# MAIN_CONN.net
KiCad netlist of a schematic drawn in Altium Designer
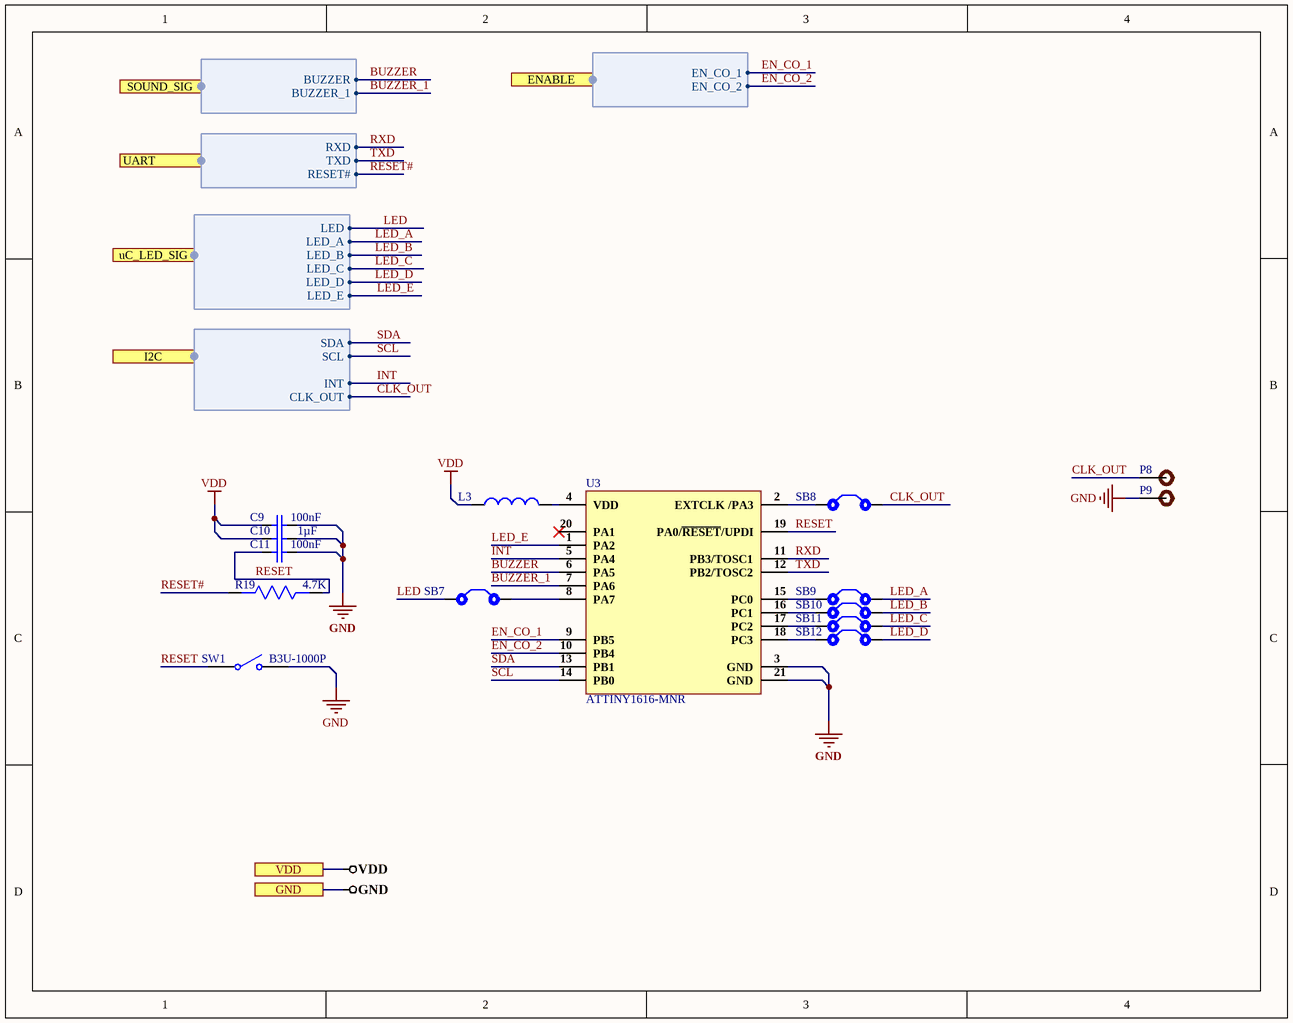
[diagram p0: MAIN_CONN.SchDoc]

(export (version "E")
  (design (tool "Eeschema 10.0.6"))
  (components
    (comp (ref "C9")
      (value "100nF")
      (footprint "Cap0402")
      (description "CAP CER 0.1UF 25V X7R 0402")
      (fields
        (field (name "MANUFACTURER") "Yageo")
        (field (name "MANUFACTURER PART NUMBER") "CC0402KRX7R8BB104")
      )
      (libsource (lib "TT_IntLib") (part "CC0402KRX7R8BB104"))
    )
    (comp (ref "C10")
      (value "1µF")
      (footprint "Cap0402")
      (description "CAP CER 1UF 25V X5R 0402")
      (fields
        (field (name "MANUFACTURER") "Murata")
        (field (name "MANUFACTURER PART NUMBER") "GRM155R61E105KA12D")
      )
      (libsource (lib "TT_IntLib") (part "GRM155R61E105KA12D"))
    )
    (comp (ref "C11")
      (value "100nF")
      (footprint "Cap0402")
      (description "CAP CER 0.1UF 25V X7R 0402")
      (fields
        (field (name "MANUFACTURER") "Yageo")
        (field (name "MANUFACTURER PART NUMBER") "CC0402KRX7R8BB104")
      )
      (libsource (lib "TT_IntLib") (part "CC0402KRX7R8BB104"))
    )
    (comp (ref "L3")
      (value "MMZ0603S601CT000")
      (footprint "IND 0201")
      (description "FERRITE BEAD 600 OHM 0201 1LN")
      (fields (field (name "MANUFACTURER") "TDK") (field (name "TOLERANCE") "25%"))
      (libsource (lib "TT_IntLib") (part "MMZ0603S601CT000"))
    )
    (comp (ref "P8")
      (value "Test Point")
      (footprint "TEST POINT")
      (description "Test Point ON")
      (libsource (lib "TT_IntLib") (part "TEST POINT"))
    )
    (comp (ref "P9")
      (value "Test Point")
      (footprint "TEST POINT")
      (description "Test Point ON")
      (libsource (lib "TT_IntLib") (part "TEST POINT"))
    )
    (comp (ref "R19")
      (value "4.7K")
      (footprint "Res-0201")
      (description "RES 4.7K OHM 1% 1/20W 0201")
      (fields
        (field (name "MANUFACTURER") "Stackpole Electronics")
        (field (name "MANUFACTURER PART NUMBER") "RMCF0201FT4K70")
      )
      (libsource (lib "TT_IntLib") (part "RMCF0201FT4K70"))
    )
    (comp (ref "SB7")
      (value "Solder Bridge")
      (footprint "Solder Bridge")
      (description "Solder Bridge ON")
      (libsource (lib "TT_IntLib") (part "Solder Bridge"))
    )
    (comp (ref "SB8")
      (value "Solder Bridge")
      (footprint "Solder Bridge")
      (description "Solder Bridge ON")
      (libsource (lib "TT_IntLib") (part "Solder Bridge"))
    )
    (comp (ref "SB9")
      (value "Solder Bridge")
      (footprint "Solder Bridge")
      (description "Solder Bridge ON")
      (libsource (lib "TT_IntLib") (part "Solder Bridge"))
    )
    (comp (ref "SB10")
      (value "Solder Bridge")
      (footprint "Solder Bridge")
      (description "Solder Bridge ON")
      (libsource (lib "TT_IntLib") (part "Solder Bridge"))
    )
    (comp (ref "SB11")
      (value "Solder Bridge")
      (footprint "Solder Bridge")
      (description "Solder Bridge ON")
      (libsource (lib "TT_IntLib") (part "Solder Bridge"))
    )
    (comp (ref "SB12")
      (value "Solder Bridge")
      (footprint "Solder Bridge")
      (description "Solder Bridge ON")
      (libsource (lib "TT_IntLib") (part "Solder Bridge"))
    )
    (comp (ref "SW1")
      (value "B3U-1000P")
      (footprint "B3U-1000P")
      (description "SWITCH TACTILE SPST-NO 0.05A 12V")
      (fields (field (name "MANUFACTURER") "Omron"))
      (libsource (lib "TT_IntLib") (part "B3U-1000P"))
    )
    (comp (ref "U3")
      (value "ATTINY1616-MNR")
      (footprint "20-QFN")
      (description "IC MCU 8BIT 16KB FLASH 20VQFN")
      (fields (field (name "MANUFACTURER") "Microchip"))
      (libsource (lib "TT_IntLib") (part "ATTINY1616-MNR"))
    )
  )
  (nets
    (net (code "6") (name "/BUZZER") (class "Default")
      (node (ref "U3") (pin "6") (pinfunction "PA5_6") (pintype "passive"))
    )
    (net (code "7") (name "/BUZZER_1") (class "Default")
      (node (ref "U3") (pin "7") (pinfunction "PA6_7") (pintype "passive"))
    )
    (net (code "8") (name "/CLK_OUT") (class "Default")
      (node (ref "P8") (pin "1") (pinfunction "1_1") (pintype "passive"))
      (node (ref "SB8") (pin "2") (pinfunction "2_2") (pintype "passive"))
    )
    (net (code "9") (name "/EN_CO_1") (class "Default")
      (node (ref "U3") (pin "9") (pinfunction "PB5_9") (pintype "passive"))
    )
    (net (code "10") (name "/EN_CO_2") (class "Default")
      (node (ref "U3") (pin "10") (pinfunction "PB4_10") (pintype "passive"))
    )
    (net (code "11") (name "/INT") (class "Default")
      (node (ref "U3") (pin "5") (pinfunction "PA4_5") (pintype "passive"))
    )
    (net (code "12") (name "/LED") (class "Default")
      (node (ref "SB7") (pin "1") (pinfunction "1_1") (pintype "passive"))
    )
    (net (code "13") (name "/LED_A") (class "Default")
      (node (ref "SB9") (pin "2") (pinfunction "2_2") (pintype "passive"))
    )
    (net (code "14") (name "/LED_B") (class "Default")
      (node (ref "SB10") (pin "2") (pinfunction "2_2") (pintype "passive"))
    )
    (net (code "15") (name "/LED_C") (class "Default")
      (node (ref "SB11") (pin "2") (pinfunction "2_2") (pintype "passive"))
    )
    (net (code "16") (name "/LED_D") (class "Default")
      (node (ref "SB12") (pin "2") (pinfunction "2_2") (pintype "passive"))
    )
    (net (code "17") (name "/LED_E") (class "Default")
      (node (ref "U3") (pin "1") (pinfunction "PA2_1") (pintype "passive"))
    )
    (net (code "18") (name "/RESET") (class "Default")
      (node (ref "C11") (pin "2") (pintype "passive"))
      (node (ref "R19") (pin "1") (pintype "passive"))
      (node (ref "SW1") (pin "1") (pinfunction "1_1") (pintype "passive"))
      (node (ref "U3") (pin "19") (pinfunction "PA0/~{RESET}/UPDI_19") (pintype "passive"))
    )
    (net (code "19") (name "/RESET#") (class "Default") (node (ref "R19") (pin "2") (pintype "passive")))
    (net (code "20") (name "/RXD") (class "Default")
      (node (ref "U3") (pin "11") (pinfunction "PB3/TOSC1_11") (pintype "passive"))
    )
    (net (code "21") (name "/SCL") (class "Default")
      (node (ref "U3") (pin "14") (pinfunction "PB0_14") (pintype "passive"))
    )
    (net (code "22") (name "/SDA") (class "Default")
      (node (ref "U3") (pin "13") (pinfunction "PB1_13") (pintype "passive"))
    )
    (net (code "23") (name "/TXD") (class "Default")
      (node (ref "U3") (pin "12") (pinfunction "PB2/TOSC2_12") (pintype "passive"))
    )
    (net (code "29") (name "GND") (class "Default")
      (node (ref "C10") (pin "1") (pintype "passive"))
      (node (ref "C11") (pin "1") (pintype "passive"))
      (node (ref "C9") (pin "1") (pintype "passive"))
      (node (ref "P9") (pin "1") (pinfunction "1_1") (pintype "passive"))
      (node (ref "SW1") (pin "2") (pinfunction "2_2") (pintype "passive"))
      (node (ref "U3") (pin "21") (pinfunction "GND_21") (pintype "passive"))
      (node (ref "U3") (pin "3") (pinfunction "GND_3") (pintype "passive"))
    )
    (net (code "30") (name "Net-(U3-EXTCLK_{slash}PA3)") (class "Default")
      (node (ref "SB8") (pin "1") (pinfunction "1_1") (pintype "passive"))
      (node (ref "U3") (pin "2") (pinfunction "EXTCLK_/PA3_2") (pintype "passive"))
    )
    (net (code "31") (name "Net-(U3-PA7)") (class "Default")
      (node (ref "SB7") (pin "2") (pinfunction "2_2") (pintype "passive"))
      (node (ref "U3") (pin "8") (pinfunction "PA7_8") (pintype "passive"))
    )
    (net (code "32") (name "Net-(U3-PC0)") (class "Default")
      (node (ref "SB9") (pin "1") (pinfunction "1_1") (pintype "passive"))
      (node (ref "U3") (pin "15") (pinfunction "PC0_15") (pintype "passive"))
    )
    (net (code "33") (name "Net-(U3-PC1)") (class "Default")
      (node (ref "SB10") (pin "1") (pinfunction "1_1") (pintype "passive"))
      (node (ref "U3") (pin "16") (pinfunction "PC1_16") (pintype "passive"))
    )
    (net (code "34") (name "Net-(U3-PC2)") (class "Default")
      (node (ref "SB11") (pin "1") (pinfunction "1_1") (pintype "passive"))
      (node (ref "U3") (pin "17") (pinfunction "PC2_17") (pintype "passive"))
    )
    (net (code "35") (name "Net-(U3-PC3)") (class "Default")
      (node (ref "SB12") (pin "1") (pinfunction "1_1") (pintype "passive"))
      (node (ref "U3") (pin "18") (pinfunction "PC3_18") (pintype "passive"))
    )
    (net (code "36") (name "Net-(U3-VDD)") (class "Default")
      (node (ref "L3") (pin "2") (pinfunction "2_2") (pintype "passive"))
      (node (ref "U3") (pin "4") (pinfunction "VDD_4") (pintype "passive"))
    )
    (net (code "37") (name "VDD") (class "Default")
      (node (ref "C10") (pin "2") (pintype "passive"))
      (node (ref "C9") (pin "2") (pintype "passive"))
      (node (ref "L3") (pin "1") (pinfunction "1_1") (pintype "passive"))
    )
    (net (code "38") (name "unconnected-(U3-PA1-Pad20)") (class "Default")
      (node (ref "U3") (pin "20") (pinfunction "PA1_20") (pintype "passive+no_connect"))
    )
  )
)
